# cable-adapter.net
KiCad netlist of a schematic drawn in EAGLE
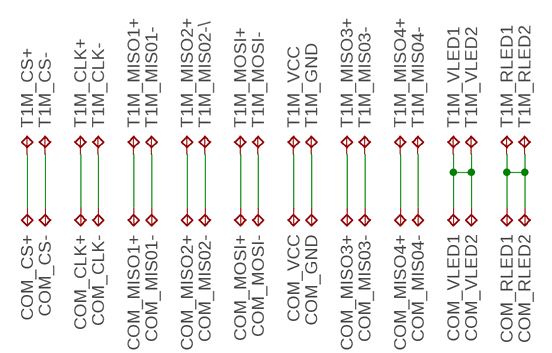
[diagram p0: schematic, sheet 1]

(export (version "E")
  (design (tool "Eeschema 10.0.6"))
  (components
    (comp (ref "COM_CLK+")
      (value "TP_SPI_WIRE+")
      (footprint "eagle-import:SPI_WIRE+")
      (libsource (lib "eagle-import") (part "TP_SPI_WIRE+"))
    )
    (comp (ref "COM_CLK-")
      (value "TP_SPI_WIRE+")
      (footprint "eagle-import:SPI_WIRE+")
      (libsource (lib "eagle-import") (part "TP_SPI_WIRE+"))
    )
    (comp (ref "COM_CS+")
      (value "TP_SPI_WIRE+")
      (footprint "eagle-import:SPI_WIRE+")
      (libsource (lib "eagle-import") (part "TP_SPI_WIRE+"))
    )
    (comp (ref "COM_CS-")
      (value "TP_SPI_WIRE+")
      (footprint "eagle-import:SPI_WIRE+")
      (libsource (lib "eagle-import") (part "TP_SPI_WIRE+"))
    )
    (comp (ref "COM_GND")
      (value "TP_SPI_WIRE+")
      (footprint "eagle-import:SPI_WIRE+")
      (libsource (lib "eagle-import") (part "TP_SPI_WIRE+"))
    )
    (comp (ref "COM_MIS01-")
      (value "TP_SPI_WIRE+")
      (footprint "eagle-import:SPI_WIRE+")
      (libsource (lib "eagle-import") (part "TP_SPI_WIRE+"))
    )
    (comp (ref "COM_MIS02-")
      (value "TP_SPI_WIRE+")
      (footprint "eagle-import:SPI_WIRE+")
      (libsource (lib "eagle-import") (part "TP_SPI_WIRE+"))
    )
    (comp (ref "COM_MIS03-")
      (value "TP_SPI_WIRE+")
      (footprint "eagle-import:SPI_WIRE+")
      (libsource (lib "eagle-import") (part "TP_SPI_WIRE+"))
    )
    (comp (ref "COM_MIS04-")
      (value "TP_SPI_WIRE+")
      (footprint "eagle-import:SPI_WIRE+")
      (libsource (lib "eagle-import") (part "TP_SPI_WIRE+"))
    )
    (comp (ref "COM_MISO1+")
      (value "TP_SPI_WIRE+")
      (footprint "eagle-import:SPI_WIRE+")
      (libsource (lib "eagle-import") (part "TP_SPI_WIRE+"))
    )
    (comp (ref "COM_MISO2+")
      (value "TP_SPI_WIRE+")
      (footprint "eagle-import:SPI_WIRE+")
      (libsource (lib "eagle-import") (part "TP_SPI_WIRE+"))
    )
    (comp (ref "COM_MISO3+")
      (value "MISO3+")
      (footprint "eagle-import:SPI_WIRE+")
      (libsource (lib "eagle-import") (part "TP_SPI_WIRE+"))
    )
    (comp (ref "COM_MISO4+")
      (value "TP_SPI_WIRE+")
      (footprint "eagle-import:SPI_WIRE+")
      (libsource (lib "eagle-import") (part "TP_SPI_WIRE+"))
    )
    (comp (ref "COM_MOSI+")
      (value "TP_SPI_WIRE+")
      (footprint "eagle-import:SPI_WIRE+")
      (libsource (lib "eagle-import") (part "TP_SPI_WIRE+"))
    )
    (comp (ref "COM_MOSI-")
      (value "TP_SPI_WIRE+")
      (footprint "eagle-import:SPI_WIRE+")
      (libsource (lib "eagle-import") (part "TP_SPI_WIRE+"))
    )
    (comp (ref "COM_RLED1")
      (value "TP_SPI_WIRE+")
      (footprint "eagle-import:SPI_WIRE+")
      (libsource (lib "eagle-import") (part "TP_SPI_WIRE+"))
    )
    (comp (ref "COM_RLED2")
      (value "TP_SPI_WIRE+")
      (footprint "eagle-import:SPI_WIRE+")
      (libsource (lib "eagle-import") (part "TP_SPI_WIRE+"))
    )
    (comp (ref "COM_VCC")
      (value "TP_SPI_WIRE+")
      (footprint "eagle-import:SPI_WIRE+")
      (libsource (lib "eagle-import") (part "TP_SPI_WIRE+"))
    )
    (comp (ref "COM_VLED1")
      (value "TP_SPI_WIRE+")
      (footprint "eagle-import:SPI_WIRE+")
      (libsource (lib "eagle-import") (part "TP_SPI_WIRE+"))
    )
    (comp (ref "COM_VLED2")
      (value "TP_SPI_WIRE+")
      (footprint "eagle-import:SPI_WIRE+")
      (libsource (lib "eagle-import") (part "TP_SPI_WIRE+"))
    )
    (comp (ref "T1M_CLK+")
      (value "TP_SPI_WIRE+")
      (footprint "eagle-import:SPI_WIRE+")
      (libsource (lib "eagle-import") (part "TP_SPI_WIRE+"))
    )
    (comp (ref "T1M_CLK-")
      (value "TP_SPI_WIRE+")
      (footprint "eagle-import:SPI_WIRE+")
      (libsource (lib "eagle-import") (part "TP_SPI_WIRE+"))
    )
    (comp (ref "T1M_CS+")
      (value "TP_SPI_WIRE+")
      (footprint "eagle-import:SPI_WIRE+")
      (libsource (lib "eagle-import") (part "TP_SPI_WIRE+"))
    )
    (comp (ref "T1M_CS-")
      (value "TP_SPI_WIRE+")
      (footprint "eagle-import:SPI_WIRE+")
      (libsource (lib "eagle-import") (part "TP_SPI_WIRE+"))
    )
    (comp (ref "T1M_GND")
      (value "TP_SPI_WIRE+")
      (footprint "eagle-import:SPI_WIRE+")
      (libsource (lib "eagle-import") (part "TP_SPI_WIRE+"))
    )
    (comp (ref "T1M_MIS01-")
      (value "TP_SPI_WIRE+")
      (footprint "eagle-import:SPI_WIRE+")
      (libsource (lib "eagle-import") (part "TP_SPI_WIRE+"))
    )
    (comp (ref "T1M_MIS02-\\")
      (value "TP_SPI_WIRE+")
      (footprint "eagle-import:SPI_WIRE+")
      (libsource (lib "eagle-import") (part "TP_SPI_WIRE+"))
    )
    (comp (ref "T1M_MIS03-")
      (value "TP_SPI_WIRE+")
      (footprint "eagle-import:SPI_WIRE+")
      (libsource (lib "eagle-import") (part "TP_SPI_WIRE+"))
    )
    (comp (ref "T1M_MIS04-")
      (value "TP_SPI_WIRE+")
      (footprint "eagle-import:SPI_WIRE+")
      (libsource (lib "eagle-import") (part "TP_SPI_WIRE+"))
    )
    (comp (ref "T1M_MISO1+")
      (value "TP_SPI_WIRE+")
      (footprint "eagle-import:SPI_WIRE+")
      (libsource (lib "eagle-import") (part "TP_SPI_WIRE+"))
    )
    (comp (ref "T1M_MISO2+")
      (value "TP_SPI_WIRE+")
      (footprint "eagle-import:SPI_WIRE+")
      (libsource (lib "eagle-import") (part "TP_SPI_WIRE+"))
    )
    (comp (ref "T1M_MISO3+")
      (value "TP_SPI_WIRE+")
      (footprint "eagle-import:SPI_WIRE+")
      (libsource (lib "eagle-import") (part "TP_SPI_WIRE+"))
    )
    (comp (ref "T1M_MISO4+")
      (value "TP_SPI_WIRE+")
      (footprint "eagle-import:SPI_WIRE+")
      (libsource (lib "eagle-import") (part "TP_SPI_WIRE+"))
    )
    (comp (ref "T1M_MOSI+")
      (value "TP_SPI_WIRE+")
      (footprint "eagle-import:SPI_WIRE+")
      (libsource (lib "eagle-import") (part "TP_SPI_WIRE+"))
    )
    (comp (ref "T1M_MOSI-")
      (value "TP_SPI_WIRE+")
      (footprint "eagle-import:SPI_WIRE+")
      (libsource (lib "eagle-import") (part "TP_SPI_WIRE+"))
    )
    (comp (ref "T1M_RLED1")
      (value "TP_SPI_WIRE+")
      (footprint "eagle-import:SPI_WIRE+")
      (libsource (lib "eagle-import") (part "TP_SPI_WIRE+"))
    )
    (comp (ref "T1M_RLED2")
      (value "TP_SPI_WIRE+")
      (footprint "eagle-import:SPI_WIRE+")
      (libsource (lib "eagle-import") (part "TP_SPI_WIRE+"))
    )
    (comp (ref "T1M_VCC")
      (value "TP_SPI_WIRE+")
      (footprint "eagle-import:SPI_WIRE+")
      (libsource (lib "eagle-import") (part "TP_SPI_WIRE+"))
    )
    (comp (ref "T1M_VLED1")
      (value "TP_SPI_WIRE+")
      (footprint "eagle-import:SPI_WIRE+")
      (libsource (lib "eagle-import") (part "TP_SPI_WIRE+"))
    )
    (comp (ref "T1M_VLED2")
      (value "TP_SPI_WIRE+")
      (footprint "eagle-import:SPI_WIRE+")
      (libsource (lib "eagle-import") (part "TP_SPI_WIRE+"))
    )
  )
  (nets
    (net (code "1") (name "Net-(COM_CLK+-TP)") (class "Default")
      (node (ref "COM_CLK+") (pin "P$1") (pinfunction "TP_P$1") (pintype "input"))
      (node (ref "T1M_CLK+") (pin "P$1") (pinfunction "TP_P$1") (pintype "input"))
    )
    (net (code "2") (name "Net-(COM_CLK--TP)") (class "Default")
      (node (ref "COM_CLK-") (pin "P$1") (pinfunction "TP_P$1") (pintype "input"))
      (node (ref "T1M_CLK-") (pin "P$1") (pinfunction "TP_P$1") (pintype "input"))
    )
    (net (code "3") (name "Net-(COM_CS+-TP)") (class "Default")
      (node (ref "COM_CS+") (pin "P$1") (pinfunction "TP_P$1") (pintype "input"))
      (node (ref "T1M_CS+") (pin "P$1") (pinfunction "TP_P$1") (pintype "input"))
    )
    (net (code "4") (name "Net-(COM_CS--TP)") (class "Default")
      (node (ref "COM_CS-") (pin "P$1") (pinfunction "TP_P$1") (pintype "input"))
      (node (ref "T1M_CS-") (pin "P$1") (pinfunction "TP_P$1") (pintype "input"))
    )
    (net (code "5") (name "Net-(COM_GND-TP)") (class "Default")
      (node (ref "COM_GND") (pin "P$1") (pinfunction "TP_P$1") (pintype "input"))
      (node (ref "T1M_GND") (pin "P$1") (pinfunction "TP_P$1") (pintype "input"))
    )
    (net (code "6") (name "Net-(COM_MIS01--TP)") (class "Default")
      (node (ref "COM_MIS01-") (pin "P$1") (pinfunction "TP_P$1") (pintype "input"))
      (node (ref "T1M_MIS01-") (pin "P$1") (pinfunction "TP_P$1") (pintype "input"))
    )
    (net (code "7") (name "Net-(COM_MIS02--TP)") (class "Default")
      (node (ref "COM_MIS02-") (pin "P$1") (pinfunction "TP_P$1") (pintype "input"))
      (node (ref "T1M_MIS02-\\") (pin "P$1") (pinfunction "TP_P$1") (pintype "input"))
    )
    (net (code "8") (name "Net-(COM_MIS03--TP)") (class "Default")
      (node (ref "COM_MIS03-") (pin "P$1") (pinfunction "TP_P$1") (pintype "input"))
      (node (ref "T1M_MIS03-") (pin "P$1") (pinfunction "TP_P$1") (pintype "input"))
    )
    (net (code "9") (name "Net-(COM_MIS04--TP)") (class "Default")
      (node (ref "COM_MIS04-") (pin "P$1") (pinfunction "TP_P$1") (pintype "input"))
      (node (ref "T1M_MIS04-") (pin "P$1") (pinfunction "TP_P$1") (pintype "input"))
    )
    (net (code "10") (name "Net-(COM_MISO1+-TP)") (class "Default")
      (node (ref "COM_MISO1+") (pin "P$1") (pinfunction "TP_P$1") (pintype "input"))
      (node (ref "T1M_MISO1+") (pin "P$1") (pinfunction "TP_P$1") (pintype "input"))
    )
    (net (code "11") (name "Net-(COM_MISO2+-TP)") (class "Default")
      (node (ref "COM_MISO2+") (pin "P$1") (pinfunction "TP_P$1") (pintype "input"))
      (node (ref "T1M_MISO2+") (pin "P$1") (pinfunction "TP_P$1") (pintype "input"))
    )
    (net (code "12") (name "Net-(COM_MISO3+-TP)") (class "Default")
      (node (ref "COM_MISO3+") (pin "P$1") (pinfunction "TP_P$1") (pintype "input"))
      (node (ref "T1M_MISO3+") (pin "P$1") (pinfunction "TP_P$1") (pintype "input"))
    )
    (net (code "13") (name "Net-(COM_MISO4+-TP)") (class "Default")
      (node (ref "COM_MISO4+") (pin "P$1") (pinfunction "TP_P$1") (pintype "input"))
      (node (ref "T1M_MISO4+") (pin "P$1") (pinfunction "TP_P$1") (pintype "input"))
    )
    (net (code "14") (name "Net-(COM_MOSI+-TP)") (class "Default")
      (node (ref "COM_MOSI+") (pin "P$1") (pinfunction "TP_P$1") (pintype "input"))
      (node (ref "T1M_MOSI+") (pin "P$1") (pinfunction "TP_P$1") (pintype "input"))
    )
    (net (code "15") (name "Net-(COM_MOSI--TP)") (class "Default")
      (node (ref "COM_MOSI-") (pin "P$1") (pinfunction "TP_P$1") (pintype "input"))
      (node (ref "T1M_MOSI-") (pin "P$1") (pinfunction "TP_P$1") (pintype "input"))
    )
    (net (code "16") (name "Net-(COM_RLED1-TP)") (class "Default")
      (node (ref "COM_RLED1") (pin "P$1") (pinfunction "TP_P$1") (pintype "input"))
      (node (ref "COM_RLED2") (pin "P$1") (pinfunction "TP_P$1") (pintype "input"))
      (node (ref "T1M_RLED1") (pin "P$1") (pinfunction "TP_P$1") (pintype "input"))
      (node (ref "T1M_RLED2") (pin "P$1") (pinfunction "TP_P$1") (pintype "input"))
    )
    (net (code "17") (name "Net-(COM_VCC-TP)") (class "Default")
      (node (ref "COM_VCC") (pin "P$1") (pinfunction "TP_P$1") (pintype "input"))
      (node (ref "T1M_VCC") (pin "P$1") (pinfunction "TP_P$1") (pintype "input"))
    )
    (net (code "18") (name "Net-(COM_VLED1-TP)") (class "Default")
      (node (ref "COM_VLED1") (pin "P$1") (pinfunction "TP_P$1") (pintype "input"))
      (node (ref "COM_VLED2") (pin "P$1") (pinfunction "TP_P$1") (pintype "input"))
      (node (ref "T1M_VLED1") (pin "P$1") (pinfunction "TP_P$1") (pintype "input"))
      (node (ref "T1M_VLED2") (pin "P$1") (pinfunction "TP_P$1") (pintype "input"))
    )
  )
)
